# LOGIC_LEVEL_CONVERTER.net
KiCad netlist of a schematic drawn in EAGLE
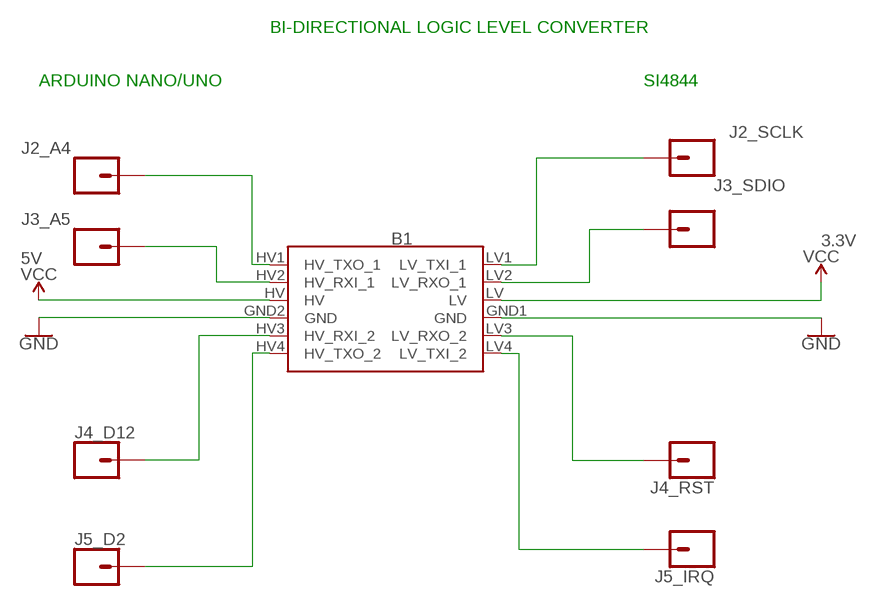
[diagram p0: schematic, sheet 1]

(export (version "E")
  (design (tool "Eeschema 10.0.6"))
  (components
    (comp (ref "B1")
      (value "SPARKFUN_LOGIC_LEVEL_CONVERTERLOCK")
      (footprint "eagle-import:SPARKFUN_LOGIC_LEVEL_CONVERTER_LOCK")
      (libsource (lib "eagle-import") (part "SPARKFUN_LOGIC_LEVEL_CONVERTERLOCK"))
    )
    (comp (ref "J2_A4")
      (value "CONN_01")
      (footprint "eagle-import:1X01")
      (libsource (lib "eagle-import") (part "CONN_01"))
    )
    (comp (ref "J2_SCLK")
      (value "CONN_01")
      (footprint "eagle-import:1X01")
      (libsource (lib "eagle-import") (part "CONN_01"))
    )
    (comp (ref "J3_A5")
      (value "CONN_01")
      (footprint "eagle-import:1X01")
      (libsource (lib "eagle-import") (part "CONN_01"))
    )
    (comp (ref "J3_SDIO")
      (value "CONN_01")
      (footprint "eagle-import:1X01")
      (libsource (lib "eagle-import") (part "CONN_01"))
    )
    (comp (ref "J4_D12")
      (value "CONN_01")
      (footprint "eagle-import:1X01")
      (libsource (lib "eagle-import") (part "CONN_01"))
    )
    (comp (ref "J4_RST")
      (value "CONN_01")
      (footprint "eagle-import:1X01")
      (libsource (lib "eagle-import") (part "CONN_01"))
    )
    (comp (ref "J5_D2")
      (value "CONN_01")
      (footprint "eagle-import:1X01")
      (libsource (lib "eagle-import") (part "CONN_01"))
    )
    (comp (ref "J5_IRQ")
      (value "CONN_01")
      (footprint "eagle-import:1X01")
      (libsource (lib "eagle-import") (part "CONN_01"))
    )
  )
  (nets
    (net (code "1") (name "GND") (class "Default")
      (node (ref "B1") (pin "GND1") (pinfunction "GND_GND1") (pintype "power_in"))
      (node (ref "B1") (pin "GND2") (pinfunction "GND_GND2") (pintype "power_in"))
    )
    (net (code "2") (name "Net-(B1-HV_RXI_1)") (class "Default")
      (node (ref "B1") (pin "HV2") (pinfunction "HV_RXI_1_HV2") (pintype "bidirectional"))
      (node (ref "J3_A5") (pin "1") (pinfunction "1_1") (pintype "passive"))
    )
    (net (code "3") (name "Net-(B1-HV_RXI_2)") (class "Default")
      (node (ref "B1") (pin "HV3") (pinfunction "HV_RXI_2_HV3") (pintype "bidirectional"))
      (node (ref "J4_D12") (pin "1") (pinfunction "1_1") (pintype "passive"))
    )
    (net (code "4") (name "Net-(B1-HV_TXO_1)") (class "Default")
      (node (ref "B1") (pin "HV1") (pinfunction "HV_TXO_1_HV1") (pintype "bidirectional"))
      (node (ref "J2_A4") (pin "1") (pinfunction "1_1") (pintype "passive"))
    )
    (net (code "5") (name "Net-(B1-HV_TXO_2)") (class "Default")
      (node (ref "B1") (pin "HV4") (pinfunction "HV_TXO_2_HV4") (pintype "bidirectional"))
      (node (ref "J5_D2") (pin "1") (pinfunction "1_1") (pintype "passive"))
    )
    (net (code "6") (name "Net-(B1-LV_RXO_1)") (class "Default")
      (node (ref "B1") (pin "LV2") (pinfunction "LV_RXO_1_LV2") (pintype "bidirectional"))
      (node (ref "J3_SDIO") (pin "1") (pinfunction "1_1") (pintype "passive"))
    )
    (net (code "7") (name "Net-(B1-LV_RXO_2)") (class "Default")
      (node (ref "B1") (pin "LV3") (pinfunction "LV_RXO_2_LV3") (pintype "bidirectional"))
      (node (ref "J4_RST") (pin "1") (pinfunction "1_1") (pintype "passive"))
    )
    (net (code "8") (name "Net-(B1-LV_TXI_1)") (class "Default")
      (node (ref "B1") (pin "LV1") (pinfunction "LV_TXI_1_LV1") (pintype "bidirectional"))
      (node (ref "J2_SCLK") (pin "1") (pinfunction "1_1") (pintype "passive"))
    )
    (net (code "9") (name "Net-(B1-LV_TXI_2)") (class "Default")
      (node (ref "B1") (pin "LV4") (pinfunction "LV_TXI_2_LV4") (pintype "bidirectional"))
      (node (ref "J5_IRQ") (pin "1") (pinfunction "1_1") (pintype "passive"))
    )
    (net (code "10") (name "VCC") (class "Default")
      (node (ref "B1") (pin "HV") (pinfunction "HV_HV") (pintype "power_in"))
      (node (ref "B1") (pin "LV") (pinfunction "LV_LV") (pintype "power_in"))
    )
  )
)
